# hello.net
KiCad netlist of a schematic drawn in EAGLE
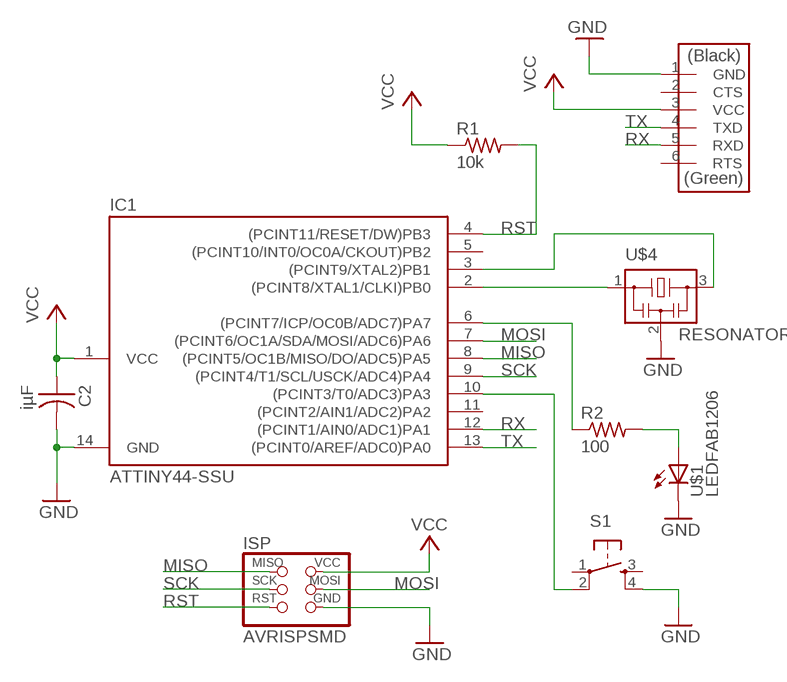
[diagram p0: schematic, sheet 1]

(export (version "E")
  (design (tool "Eeschema 10.0.6"))
  (components
    (comp (ref "C2")
      (value "iµF")
      (footprint "eagle-import:C1206")
      (libsource (lib "eagle-import") (part "CAP-US1206"))
    )
    (comp (ref "IC1")
      (value "ATTINY44-SSU")
      (footprint "eagle-import:SOIC14")
      (libsource (lib "eagle-import") (part "ATTINY44-SSU"))
    )
    (comp (ref "ISP")
      (value "AVRISPSMD")
      (footprint "eagle-import:2X03SMD")
      (libsource (lib "eagle-import") (part "AVRISPSMD"))
    )
    (comp (ref "R1")
      (value "10k")
      (footprint "eagle-import:R1206")
      (libsource (lib "eagle-import") (part "RES-US1206"))
    )
    (comp (ref "R2")
      (value "100")
      (footprint "eagle-import:R1206")
      (libsource (lib "eagle-import") (part "RES-US1206"))
    )
    (comp (ref "S1")
      (value "6MM_SWITCH6MM_SWITCH")
      (footprint "eagle-import:6MM_SWITCH")
      (libsource (lib "eagle-import") (part "6MM_SWITCH6MM_SWITCH"))
    )
    (comp (ref "U$1")
      (value "LEDFAB1206")
      (footprint "eagle-import:LED1206FAB")
      (libsource (lib "eagle-import") (part "LEDFAB1206"))
    )
    (comp (ref "U$2")
      (value "FTDI-SMD-HEADER")
      (footprint "eagle-import:1X06SMD")
      (libsource (lib "eagle-import") (part "FTDI-SMD-HEADER"))
    )
    (comp (ref "U$4")
      (value "RESONATOR")
      (footprint "eagle-import:EFOBM")
      (libsource (lib "eagle-import") (part "RESONATOR"))
    )
  )
  (nets
    (net (code "1") (name "/MISO") (class "Default")
      (node (ref "IC1") (pin "8") (pinfunction "(PCINT5/OC1B/MISO/DO/ADC5)PA5_8") (pintype "bidirectional"))
      (node (ref "ISP") (pin "1") (pinfunction "MISO_1") (pintype "passive"))
    )
    (net (code "2") (name "/MOSI") (class "Default")
      (node (ref "IC1") (pin "7") (pinfunction "(PCINT6/OC1A/SDA/MOSI/ADC6)PA6_7") (pintype "bidirectional"))
      (node (ref "ISP") (pin "4") (pinfunction "MOSI_4") (pintype "passive"))
    )
    (net (code "3") (name "/RST") (class "Default")
      (node (ref "IC1") (pin "4") (pinfunction "(PCINT11/RESET/DW)PB3_4") (pintype "bidirectional"))
      (node (ref "ISP") (pin "5") (pinfunction "RST_5") (pintype "passive"))
      (node (ref "R1") (pin "2") (pinfunction "2_2") (pintype "passive"))
    )
    (net (code "4") (name "/RX") (class "Default")
      (node (ref "IC1") (pin "12") (pinfunction "(PCINT1/AIN0/ADC1)PA1_12") (pintype "bidirectional"))
      (node (ref "U$2") (pin "5") (pinfunction "RXD_5") (pintype "bidirectional"))
    )
    (net (code "5") (name "/SCK") (class "Default")
      (node (ref "IC1") (pin "9") (pinfunction "(PCINT4/T1/SCL/USCK/ADC4)PA4_9") (pintype "bidirectional"))
      (node (ref "ISP") (pin "3") (pinfunction "SCK_3") (pintype "passive"))
    )
    (net (code "6") (name "/TX") (class "Default")
      (node (ref "IC1") (pin "13") (pinfunction "(PCINT0/AREF/ADC0)PA0_13") (pintype "bidirectional"))
      (node (ref "U$2") (pin "4") (pinfunction "TXD_4") (pintype "bidirectional"))
    )
    (net (code "7") (name "GND") (class "Default")
      (node (ref "C2") (pin "2") (pinfunction "2_2") (pintype "passive"))
      (node (ref "IC1") (pin "14") (pinfunction "GND_14") (pintype "power_in"))
      (node (ref "ISP") (pin "6") (pinfunction "GND_6") (pintype "passive"))
      (node (ref "S1") (pin "4") (pinfunction "S1_4") (pintype "passive"))
      (node (ref "U$1") (pin "2") (pinfunction "C_2") (pintype "passive"))
      (node (ref "U$2") (pin "1") (pinfunction "GND_1") (pintype "bidirectional"))
      (node (ref "U$4") (pin "2") (pinfunction "2_2") (pintype "passive"))
    )
    (net (code "8") (name "Net-(IC1-(PCINT3{slash}T0{slash}ADC3)PA3)") (class "Default")
      (node (ref "IC1") (pin "10") (pinfunction "(PCINT3/T0/ADC3)PA3_10") (pintype "bidirectional"))
      (node (ref "S1") (pin "2") (pinfunction "P1_2") (pintype "passive"))
    )
    (net (code "9") (name "Net-(IC1-(PCINT7{slash}ICP{slash}OC0B{slash}ADC7)PA7)") (class "Default")
      (node (ref "IC1") (pin "6") (pinfunction "(PCINT7/ICP/OC0B/ADC7)PA7_6") (pintype "bidirectional"))
      (node (ref "R2") (pin "1") (pinfunction "1_1") (pintype "passive"))
    )
    (net (code "10") (name "Net-(IC1-(PCINT8{slash}XTAL1{slash}CLKI)PB0)") (class "Default")
      (node (ref "IC1") (pin "2") (pinfunction "(PCINT8/XTAL1/CLKI)PB0_2") (pintype "bidirectional"))
      (node (ref "U$4") (pin "1") (pinfunction "1_1") (pintype "passive"))
    )
    (net (code "11") (name "Net-(IC1-(PCINT9{slash}XTAL2)PB1)") (class "Default")
      (node (ref "IC1") (pin "3") (pinfunction "(PCINT9/XTAL2)PB1_3") (pintype "bidirectional"))
      (node (ref "U$4") (pin "3") (pinfunction "3_3") (pintype "passive"))
    )
    (net (code "12") (name "Net-(U$1-A)") (class "Default")
      (node (ref "R2") (pin "2") (pinfunction "2_2") (pintype "passive"))
      (node (ref "U$1") (pin "1") (pinfunction "A_1") (pintype "passive"))
    )
    (net (code "13") (name "VCC") (class "Default")
      (node (ref "C2") (pin "1") (pinfunction "1_1") (pintype "passive"))
      (node (ref "IC1") (pin "1") (pinfunction "VCC_1") (pintype "power_in"))
      (node (ref "ISP") (pin "2") (pinfunction "VCC_2") (pintype "passive"))
      (node (ref "R1") (pin "1") (pinfunction "1_1") (pintype "passive"))
      (node (ref "U$2") (pin "3") (pinfunction "VCC_3") (pintype "bidirectional"))
    )
    (net (code "14") (name "unconnected-(IC1-(PCINT2{slash}AIN1{slash}ADC2)PA2-Pad11)") (class "Default")
      (node (ref "IC1") (pin "11") (pinfunction "(PCINT2/AIN1/ADC2)PA2_11") (pintype "bidirectional"))
    )
    (net (code "15") (name "unconnected-(IC1-(PCINT10{slash}INT0{slash}OC0A{slash}CKOUT)PB2-Pad5)") (class "Default")
      (node (ref "IC1") (pin "5") (pinfunction "(PCINT10/INT0/OC0A/CKOUT)PB2_5") (pintype "bidirectional"))
    )
    (net (code "16") (name "unconnected-(S1-P-Pad1)") (class "Default")
      (node (ref "S1") (pin "1") (pinfunction "P_1") (pintype "passive"))
    )
    (net (code "17") (name "unconnected-(S1-S-Pad3)") (class "Default")
      (node (ref "S1") (pin "3") (pinfunction "S_3") (pintype "passive"))
    )
    (net (code "18") (name "unconnected-(U$2-CTS-Pad2)") (class "Default")
      (node (ref "U$2") (pin "2") (pinfunction "CTS_2") (pintype "bidirectional"))
    )
    (net (code "19") (name "unconnected-(U$2-RTS-Pad6)") (class "Default")
      (node (ref "U$2") (pin "6") (pinfunction "RTS_6") (pintype "bidirectional"))
    )
  )
)
